# Power.net
KiCad netlist of a schematic drawn in Altium Designer
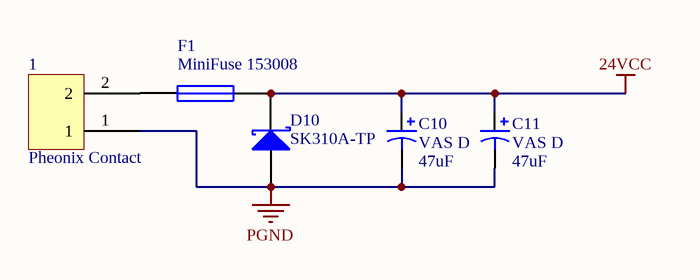
[diagram p0: Power.SchDoc]

(export (version "E")
  (design (tool "Eeschema 10.0.6"))
  (components
    (comp (ref "1")
      (value "Pheonix Contact")
      (footprint "con-phoenix-508")
      (libsource (lib "Ribbon Breakout Schem Symbols") (part "Pheonix Contact 2X1"))
    )
    (comp (ref "C10")
      (value "VAS D")
      (footprint "Panasonic VS D")
      (description "Polarized Capacitor (Radial)")
      (fields (field (name "ALTIUM_VALUE") "47uF") (field (name "PUBLISHER") "Altium Limited"))
      (libsource (lib "Miscellaneous Devices") (part "Cap Pol1"))
    )
    (comp (ref "C11")
      (value "VAS D")
      (footprint "Panasonic VS D")
      (description "Polarized Capacitor (Radial)")
      (fields (field (name "ALTIUM_VALUE") "47uF") (field (name "PUBLISHER") "Altium Limited"))
      (libsource (lib "Miscellaneous Devices") (part "Cap Pol1"))
    )
    (comp (ref "D10")
      (value "SK310A-TP")
      (footprint "SK310A-TP")
      (description "Schottky Diode")
      (fields (field (name "PUBLISHER") "Altium Limited"))
      (libsource (lib "Miscellaneous Devices") (part "D Schottky"))
    )
    (comp (ref "F1")
      (value "MiniFuse 153008")
      (footprint "TinyFuseATO_Carrier")
      (description "Fuse")
      (fields (field (name "PUBLISHER") "Altium Limited"))
      (libsource (lib "Miscellaneous Devices") (part "Fuse 1"))
    )
  )
  (nets
    (net (code "1") (name "24VCC") (class "Default")
      (node (ref "C10") (pin "1") (pinfunction "1_1") (pintype "passive"))
      (node (ref "C11") (pin "1") (pinfunction "1_1") (pintype "passive"))
      (node (ref "D10") (pin "2") (pinfunction "K_2") (pintype "passive"))
      (node (ref "F1") (pin "2") (pinfunction "2_2") (pintype "passive"))
    )
    (net (code "2") (name "Net-(1-Pad2)") (class "Default")
      (node (ref "1") (pin "2") (pinfunction "2_2") (pintype "passive"))
      (node (ref "F1") (pin "1") (pinfunction "1_1") (pintype "passive"))
    )
    (net (code "3") (name "PGND") (class "Default")
      (node (ref "1") (pin "1") (pinfunction "1_1") (pintype "passive"))
      (node (ref "C10") (pin "2") (pinfunction "2_2") (pintype "passive"))
      (node (ref "C11") (pin "2") (pinfunction "2_2") (pintype "passive"))
      (node (ref "D10") (pin "1") (pinfunction "A_1") (pintype "passive"))
    )
  )
)
